# Power.net
KiCad netlist of a schematic drawn in Altium Designer
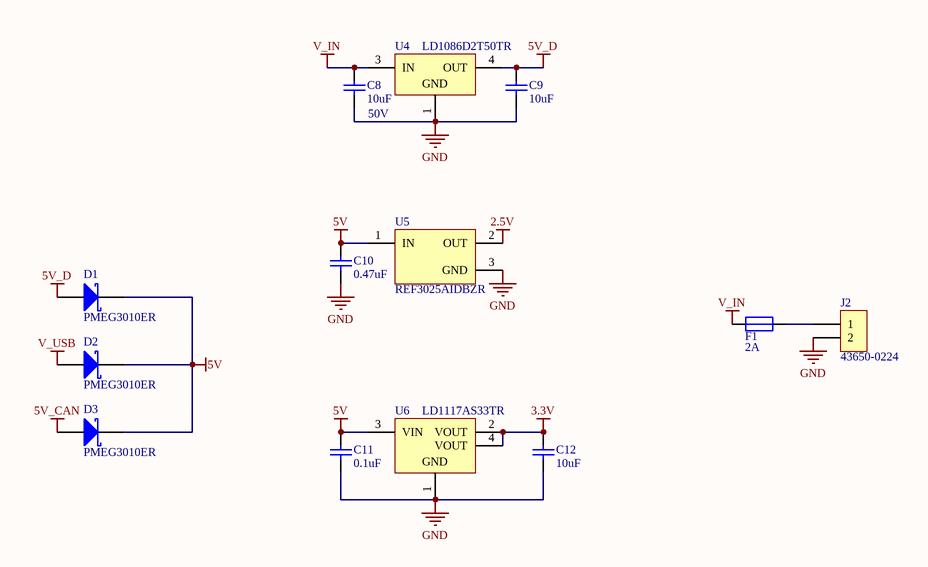
[diagram p0: Power.SchDoc]

(export (version "E")
  (design (tool "Eeschema 10.0.6"))
  (components
    (comp (ref "C8")
      (value "10uF")
      (footprint "1206_CAP")
      (fields (field (name "MAX_V") "50V") (field (name "Comment") "Capacitor"))
      (libsource (lib "Passive_comp") (part "Capacitor"))
    )
    (comp (ref "C9")
      (value "10uF")
      (footprint "1206_CAP")
      (fields (field (name "Comment") "Capacitor"))
      (libsource (lib "Passive_comp") (part "Capacitor"))
    )
    (comp (ref "C10")
      (value "0.47uF")
      (footprint "0603_CAP")
      (fields (field (name "Comment") "Capacitor"))
      (libsource (lib "Passive_comp") (part "Capacitor"))
    )
    (comp (ref "C11")
      (value "0.1uF")
      (footprint "0603_CAP")
      (fields (field (name "Comment") "Capacitor"))
      (libsource (lib "Passive_comp") (part "Capacitor"))
    )
    (comp (ref "C12")
      (value "10uF")
      (footprint "1206_CAP")
      (fields (field (name "Comment") "Capacitor"))
      (libsource (lib "Passive_comp") (part "Capacitor"))
    )
    (comp (ref "D1")
      (value "PMEG3010ER")
      (footprint "SOD123W")
      (description "Schottky Diode")
      (fields (field (name "PUBLISHER") "Altium Limited"))
      (libsource (lib "Passive_comp") (part "D Schottky"))
    )
    (comp (ref "D2")
      (value "PMEG3010ER")
      (footprint "SOD123W")
      (description "Schottky Diode")
      (fields (field (name "PUBLISHER") "Altium Limited"))
      (libsource (lib "Passive_comp") (part "D Schottky"))
    )
    (comp (ref "D3")
      (value "PMEG3010ER")
      (footprint "SOD123W")
      (description "Schottky Diode")
      (fields (field (name "PUBLISHER") "Altium Limited"))
      (libsource (lib "Passive_comp") (part "D Schottky"))
    )
    (comp (ref "F1") (value "2A") (footprint "0603_RES") (libsource (lib "Passive_comp") (part "Fuse")))
    (comp (ref "J2")
      (value "43650-0224")
      (footprint "43650-0224")
      (description "Molex - Micro-Fit 3.0 Series connector,  3.00mm (0.118\") pitch header, 2 positions.")
      (libsource (lib "con-molex-micro-fit-3_0") (part "HEADER_POS2_?43650-0224"))
    )
    (comp (ref "U4")
      (value "LD1086D2T50TR")
      (footprint "TO-263_N")
      (description "1.5A, Low Drop Positive Voltage Regulator, 5.0V, 3-Pin D2PAK, Tape and Reel")
      (libsource (lib "Altium Content Vault") (part "PM-REG-LD1085-SOT3"))
    )
    (comp (ref "U5")
      (value "REF3025AIDBZR")
      (footprint "TI-DBZ3_N")
      (fields (field (name "MANUFACTURER") "Texas Instruments"))
      (libsource (lib "Altium Content Vault") (part "TI-REF3025DBZ3"))
    )
    (comp (ref "U6")
      (value "LD1117AS33TR")
      (footprint "SOT-223_M")
      (description "1A, Low Drop Positive Voltage Regulator, 3.3V, 4-Pin SOT-223, Tape and Reel")
      (libsource (lib "Altium Content Vault") (part "PM-REG-LD1117-SOT4"))
    )
  )
  (nets
    (net (code "1") (name "2.5V") (class "Default")
      (node (ref "U5") (pin "2") (pinfunction "OUT_2") (pintype "power_in"))
    )
    (net (code "2") (name "3.3V") (class "Default")
      (node (ref "C12") (pin "2") (pinfunction "2_2") (pintype "passive"))
      (node (ref "U6") (pin "2") (pinfunction "VOUT_2") (pintype "power_in"))
      (node (ref "U6") (pin "4") (pinfunction "VOUT_4") (pintype "power_in"))
    )
    (net (code "3") (name "5V") (class "Default")
      (node (ref "C10") (pin "2") (pinfunction "2_2") (pintype "passive"))
      (node (ref "C11") (pin "2") (pinfunction "2_2") (pintype "passive"))
      (node (ref "D1") (pin "1") (pinfunction "K_1") (pintype "passive"))
      (node (ref "D2") (pin "1") (pinfunction "K_1") (pintype "passive"))
      (node (ref "D3") (pin "1") (pinfunction "K_1") (pintype "passive"))
      (node (ref "U5") (pin "1") (pinfunction "IN_1") (pintype "power_in"))
      (node (ref "U6") (pin "3") (pinfunction "VIN_3") (pintype "power_in"))
    )
    (net (code "4") (name "5V_CAN") (class "Default")
      (node (ref "D3") (pin "2") (pinfunction "A_2") (pintype "passive"))
    )
    (net (code "5") (name "5V_D") (class "Default")
      (node (ref "C9") (pin "2") (pinfunction "2_2") (pintype "passive"))
      (node (ref "D1") (pin "2") (pinfunction "A_2") (pintype "passive"))
      (node (ref "U4") (pin "4") (pinfunction "OUT_4") (pintype "power_in"))
    )
    (net (code "6") (name "GND") (class "Default")
      (node (ref "C10") (pin "1") (pinfunction "1_1") (pintype "passive"))
      (node (ref "C11") (pin "1") (pinfunction "1_1") (pintype "passive"))
      (node (ref "C12") (pin "1") (pinfunction "1_1") (pintype "passive"))
      (node (ref "C8") (pin "1") (pinfunction "1_1") (pintype "passive"))
      (node (ref "C9") (pin "1") (pinfunction "1_1") (pintype "passive"))
      (node (ref "J2") (pin "2") (pinfunction "2_2") (pintype "passive"))
      (node (ref "U4") (pin "1") (pinfunction "GND_1") (pintype "power_in"))
      (node (ref "U5") (pin "3") (pinfunction "GND_3") (pintype "power_in"))
      (node (ref "U6") (pin "1") (pinfunction "GND_1") (pintype "power_in"))
    )
    (net (code "7") (name "Net-(F1-Pad2)") (class "Default")
      (node (ref "F1") (pin "2") (pinfunction "2_2") (pintype "passive"))
      (node (ref "J2") (pin "1") (pinfunction "1_1") (pintype "passive"))
    )
    (net (code "8") (name "V_IN") (class "Default")
      (node (ref "C8") (pin "2") (pinfunction "2_2") (pintype "passive"))
      (node (ref "F1") (pin "1") (pinfunction "1_1") (pintype "passive"))
      (node (ref "U4") (pin "3") (pinfunction "IN_3") (pintype "power_in"))
    )
    (net (code "9") (name "V_USB") (class "Default")
      (node (ref "D2") (pin "2") (pinfunction "A_2") (pintype "passive"))
    )
  )
)
